# J65ACIA.net
KiCad netlist of a schematic drawn in Altium Designer
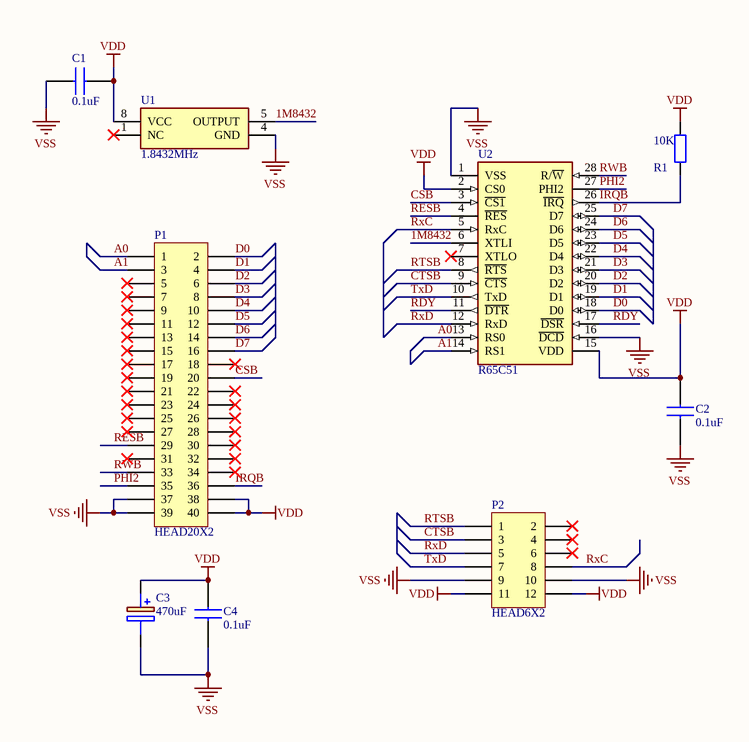
[diagram p0: J65ACIA.SchDoc]

(export (version "E")
  (design (tool "Eeschema 10.0.6"))
  (components
    (comp (ref "C1") (value "0.1uF") (footprint "SamacSys:CAP508") (libsource (lib "SamacSys") (part "CAP1")))
    (comp (ref "C2") (value "0.1uF") (footprint "SamacSys:CAP508") (libsource (lib "SamacSys") (part "CAP1")))
    (comp (ref "C3")
      (value "470uF")
      (footprint "SamacSys:CAP8X12")
      (libsource (lib "SamacSys") (part "CAP2"))
    )
    (comp (ref "C4") (value "0.1uF") (footprint "SamacSys:CAP508") (libsource (lib "SamacSys") (part "CAP1")))
    (comp (ref "P1")
      (value "HEAD20X2")
      (footprint "HD20X2")
      (fields (field (name "PUBLISHER") "Altium Limited"))
      (libsource (lib "SamacSys") (part "HEAD20X2"))
    )
    (comp (ref "P2")
      (value "HEAD6X2")
      (footprint "HD6X2")
      (fields (field (name "PUBLISHER") "Altium Limited"))
      (libsource (lib "SamacSys") (part "HEAD6X2"))
    )
    (comp (ref "R1")
      (value "10K")
      (footprint "SamacSys:AXIAL-0.4")
      (libsource (lib "SamacSys") (part "RES1"))
    )
    (comp (ref "U1")
      (value "1.8432MHz")
      (footprint "SamacSys:OSC4P")
      (libsource (lib "SamacSys") (part "OSCX"))
    )
    (comp (ref "U2")
      (value "R65C51")
      (footprint "SamacSys:DIP28V")
      (libsource (lib "SamacSys") (part "R65C51"))
    )
  )
  (nets
    (net (code "1") (name "/1M8432") (class "Default")
      (node (ref "U1") (pin "5") (pinfunction "OUTPUT_5") (pintype "passive"))
      (node (ref "U2") (pin "6") (pinfunction "XTLI_6") (pintype "passive"))
    )
    (net (code "2") (name "/A0") (class "Default")
      (node (ref "P1") (pin "1") (pinfunction "1_1") (pintype "passive"))
      (node (ref "U2") (pin "13") (pinfunction "RS0_13") (pintype "input"))
    )
    (net (code "3") (name "/A1") (class "Default")
      (node (ref "P1") (pin "3") (pinfunction "3_3") (pintype "passive"))
      (node (ref "U2") (pin "14") (pinfunction "RS1_14") (pintype "input"))
    )
    (net (code "4") (name "/CSB") (class "Default")
      (node (ref "P1") (pin "20") (pinfunction "20_20") (pintype "passive"))
      (node (ref "U2") (pin "3") (pinfunction "~{CS1}_3") (pintype "input"))
    )
    (net (code "5") (name "/CTSB") (class "Default")
      (node (ref "P2") (pin "3") (pinfunction "3_3") (pintype "passive"))
      (node (ref "U2") (pin "9") (pinfunction "~{CTS}_9") (pintype "input"))
    )
    (net (code "6") (name "/D0") (class "Default")
      (node (ref "P1") (pin "2") (pinfunction "2_2") (pintype "passive"))
      (node (ref "U2") (pin "18") (pinfunction "D0_18") (pintype "bidirectional"))
    )
    (net (code "7") (name "/D1") (class "Default")
      (node (ref "P1") (pin "4") (pinfunction "4_4") (pintype "passive"))
      (node (ref "U2") (pin "19") (pinfunction "D1_19") (pintype "bidirectional"))
    )
    (net (code "8") (name "/D2") (class "Default")
      (node (ref "P1") (pin "6") (pinfunction "6_6") (pintype "passive"))
      (node (ref "U2") (pin "20") (pinfunction "D2_20") (pintype "bidirectional"))
    )
    (net (code "9") (name "/D3") (class "Default")
      (node (ref "P1") (pin "8") (pinfunction "8_8") (pintype "passive"))
      (node (ref "U2") (pin "21") (pinfunction "D3_21") (pintype "bidirectional"))
    )
    (net (code "10") (name "/D4") (class "Default")
      (node (ref "P1") (pin "10") (pinfunction "10_10") (pintype "passive"))
      (node (ref "U2") (pin "22") (pinfunction "D4_22") (pintype "bidirectional"))
    )
    (net (code "11") (name "/D5") (class "Default")
      (node (ref "P1") (pin "12") (pinfunction "12_12") (pintype "passive"))
      (node (ref "U2") (pin "23") (pinfunction "D5_23") (pintype "bidirectional"))
    )
    (net (code "12") (name "/D6") (class "Default")
      (node (ref "P1") (pin "14") (pinfunction "14_14") (pintype "passive"))
      (node (ref "U2") (pin "24") (pinfunction "D6_24") (pintype "bidirectional"))
    )
    (net (code "13") (name "/D7") (class "Default")
      (node (ref "P1") (pin "16") (pinfunction "16_16") (pintype "passive"))
      (node (ref "U2") (pin "25") (pinfunction "D7_25") (pintype "bidirectional"))
    )
    (net (code "14") (name "/IRQB") (class "Default")
      (node (ref "P1") (pin "36") (pinfunction "36_36") (pintype "passive"))
      (node (ref "R1") (pin "2") (pinfunction "2_2") (pintype "passive"))
      (node (ref "U2") (pin "26") (pinfunction "~{IRQ}_26") (pintype "output"))
    )
    (net (code "15") (name "/PHI2") (class "Default")
      (node (ref "P1") (pin "35") (pinfunction "35_35") (pintype "passive"))
      (node (ref "U2") (pin "27") (pinfunction "PHI2_27") (pintype "passive"))
    )
    (net (code "16") (name "/RDY") (class "Default")
      (node (ref "U2") (pin "11") (pinfunction "~{DTR}_11") (pintype "output"))
      (node (ref "U2") (pin "17") (pinfunction "~{DSR}_17") (pintype "input"))
    )
    (net (code "17") (name "/RESB") (class "Default")
      (node (ref "P1") (pin "29") (pinfunction "29_29") (pintype "passive"))
      (node (ref "U2") (pin "4") (pinfunction "~{RES}_4") (pintype "passive"))
    )
    (net (code "18") (name "/RTSB") (class "Default")
      (node (ref "P2") (pin "1") (pinfunction "1_1") (pintype "passive"))
      (node (ref "U2") (pin "8") (pinfunction "~{RTS}_8") (pintype "output"))
    )
    (net (code "19") (name "/RWB") (class "Default")
      (node (ref "P1") (pin "33") (pinfunction "33_33") (pintype "passive"))
      (node (ref "U2") (pin "28") (pinfunction "R/~{W}_28") (pintype "input"))
    )
    (net (code "20") (name "/RxC") (class "Default")
      (node (ref "P2") (pin "8") (pinfunction "8_8") (pintype "passive"))
      (node (ref "U2") (pin "5") (pinfunction "RxC_5") (pintype "input"))
    )
    (net (code "21") (name "/RxD") (class "Default")
      (node (ref "P2") (pin "5") (pinfunction "5_5") (pintype "passive"))
      (node (ref "U2") (pin "12") (pinfunction "RxD_12") (pintype "input"))
    )
    (net (code "22") (name "/TxD") (class "Default")
      (node (ref "P2") (pin "7") (pinfunction "7_7") (pintype "passive"))
      (node (ref "U2") (pin "10") (pinfunction "TxD_10") (pintype "output"))
    )
    (net (code "23") (name "VDD") (class "Default")
      (node (ref "C1") (pin "1") (pinfunction "1_1") (pintype "passive"))
      (node (ref "C2") (pin "1") (pinfunction "1_1") (pintype "passive"))
      (node (ref "C3") (pin "1") (pinfunction "+_1") (pintype "passive"))
      (node (ref "C4") (pin "1") (pinfunction "1_1") (pintype "passive"))
      (node (ref "P1") (pin "38") (pinfunction "38_38") (pintype "passive"))
      (node (ref "P1") (pin "40") (pinfunction "40_40") (pintype "passive"))
      (node (ref "P2") (pin "11") (pinfunction "11_11") (pintype "passive"))
      (node (ref "P2") (pin "12") (pinfunction "12_12") (pintype "passive"))
      (node (ref "R1") (pin "1") (pinfunction "1_1") (pintype "passive"))
      (node (ref "U1") (pin "8") (pinfunction "VCC_8") (pintype "passive"))
      (node (ref "U2") (pin "15") (pinfunction "VDD_15") (pintype "passive"))
      (node (ref "U2") (pin "2") (pinfunction "CS0_2") (pintype "input"))
    )
    (net (code "24") (name "VSS") (class "Default")
      (node (ref "C1") (pin "2") (pinfunction "2_2") (pintype "passive"))
      (node (ref "C2") (pin "2") (pinfunction "2_2") (pintype "passive"))
      (node (ref "C3") (pin "2") (pinfunction "-_2") (pintype "passive"))
      (node (ref "C4") (pin "2") (pinfunction "2_2") (pintype "passive"))
      (node (ref "P1") (pin "37") (pinfunction "37_37") (pintype "passive"))
      (node (ref "P1") (pin "39") (pinfunction "39_39") (pintype "passive"))
      (node (ref "P2") (pin "10") (pinfunction "10_10") (pintype "passive"))
      (node (ref "P2") (pin "9") (pinfunction "9_9") (pintype "passive"))
      (node (ref "U1") (pin "4") (pinfunction "GND_4") (pintype "passive"))
      (node (ref "U2") (pin "1") (pinfunction "VSS_1") (pintype "passive"))
      (node (ref "U2") (pin "16") (pinfunction "~{DCD}_16") (pintype "input"))
    )
    (net (code "25") (name "unconnected-(P1-Pad5)") (class "Default")
      (node (ref "P1") (pin "5") (pinfunction "5_5") (pintype "passive+no_connect"))
    )
    (net (code "26") (name "unconnected-(P1-Pad7)") (class "Default")
      (node (ref "P1") (pin "7") (pinfunction "7_7") (pintype "passive+no_connect"))
    )
    (net (code "27") (name "unconnected-(P1-Pad9)") (class "Default")
      (node (ref "P1") (pin "9") (pinfunction "9_9") (pintype "passive+no_connect"))
    )
    (net (code "28") (name "unconnected-(P1-Pad11)") (class "Default")
      (node (ref "P1") (pin "11") (pinfunction "11_11") (pintype "passive+no_connect"))
    )
    (net (code "29") (name "unconnected-(P1-Pad13)") (class "Default")
      (node (ref "P1") (pin "13") (pinfunction "13_13") (pintype "passive+no_connect"))
    )
    (net (code "30") (name "unconnected-(P1-Pad15)") (class "Default")
      (node (ref "P1") (pin "15") (pinfunction "15_15") (pintype "passive+no_connect"))
    )
    (net (code "31") (name "unconnected-(P1-Pad17)") (class "Default")
      (node (ref "P1") (pin "17") (pinfunction "17_17") (pintype "passive+no_connect"))
    )
    (net (code "32") (name "unconnected-(P1-Pad18)") (class "Default")
      (node (ref "P1") (pin "18") (pinfunction "18_18") (pintype "passive+no_connect"))
    )
    (net (code "33") (name "unconnected-(P1-Pad19)") (class "Default")
      (node (ref "P1") (pin "19") (pinfunction "19_19") (pintype "passive+no_connect"))
    )
    (net (code "34") (name "unconnected-(P1-Pad21)") (class "Default")
      (node (ref "P1") (pin "21") (pinfunction "21_21") (pintype "passive+no_connect"))
    )
    (net (code "35") (name "unconnected-(P1-Pad22)") (class "Default")
      (node (ref "P1") (pin "22") (pinfunction "22_22") (pintype "passive+no_connect"))
    )
    (net (code "36") (name "unconnected-(P1-Pad23)") (class "Default")
      (node (ref "P1") (pin "23") (pinfunction "23_23") (pintype "passive+no_connect"))
    )
    (net (code "37") (name "unconnected-(P1-Pad24)") (class "Default")
      (node (ref "P1") (pin "24") (pinfunction "24_24") (pintype "passive+no_connect"))
    )
    (net (code "38") (name "unconnected-(P1-Pad25)") (class "Default")
      (node (ref "P1") (pin "25") (pinfunction "25_25") (pintype "passive+no_connect"))
    )
    (net (code "39") (name "unconnected-(P1-Pad26)") (class "Default")
      (node (ref "P1") (pin "26") (pinfunction "26_26") (pintype "passive+no_connect"))
    )
    (net (code "40") (name "unconnected-(P1-Pad27)") (class "Default")
      (node (ref "P1") (pin "27") (pinfunction "27_27") (pintype "passive+no_connect"))
    )
    (net (code "41") (name "unconnected-(P1-Pad28)") (class "Default")
      (node (ref "P1") (pin "28") (pinfunction "28_28") (pintype "passive+no_connect"))
    )
    (net (code "42") (name "unconnected-(P1-Pad30)") (class "Default")
      (node (ref "P1") (pin "30") (pinfunction "30_30") (pintype "passive+no_connect"))
    )
    (net (code "43") (name "unconnected-(P1-Pad31)") (class "Default")
      (node (ref "P1") (pin "31") (pinfunction "31_31") (pintype "passive+no_connect"))
    )
    (net (code "44") (name "unconnected-(P1-Pad32)") (class "Default")
      (node (ref "P1") (pin "32") (pinfunction "32_32") (pintype "passive+no_connect"))
    )
    (net (code "45") (name "unconnected-(P1-Pad34)") (class "Default")
      (node (ref "P1") (pin "34") (pinfunction "34_34") (pintype "passive+no_connect"))
    )
    (net (code "46") (name "unconnected-(P2-Pad2)") (class "Default")
      (node (ref "P2") (pin "2") (pinfunction "2_2") (pintype "passive+no_connect"))
    )
    (net (code "47") (name "unconnected-(P2-Pad4)") (class "Default")
      (node (ref "P2") (pin "4") (pinfunction "4_4") (pintype "passive+no_connect"))
    )
    (net (code "48") (name "unconnected-(P2-Pad6)") (class "Default")
      (node (ref "P2") (pin "6") (pinfunction "6_6") (pintype "passive+no_connect"))
    )
    (net (code "49") (name "unconnected-(U1-NC-Pad1)") (class "Default")
      (node (ref "U1") (pin "1") (pinfunction "NC_1") (pintype "passive+no_connect"))
    )
    (net (code "50") (name "unconnected-(U2-XTLO-Pad7)") (class "Default")
      (node (ref "U2") (pin "7") (pinfunction "XTLO_7") (pintype "passive+no_connect"))
    )
  )
)
